# Sheet1.net
KiCad netlist of a schematic drawn in Altium Designer
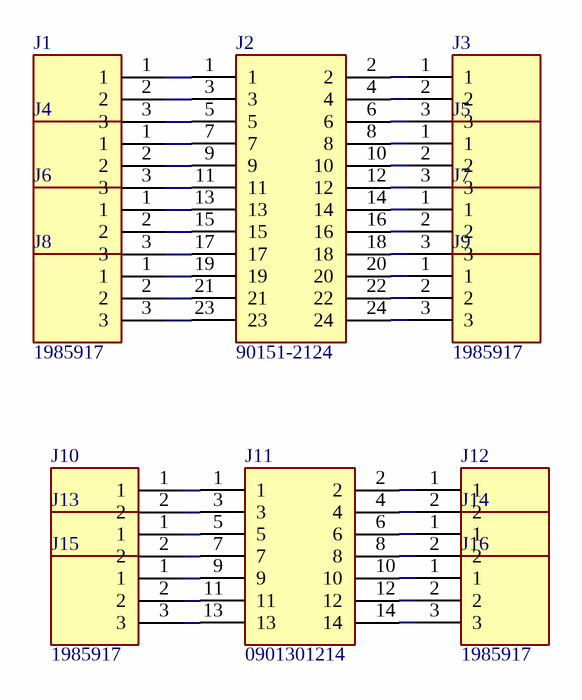
[diagram p0: Sheet1.SchDoc]

(export (version "E")
  (design (tool "Eeschema 10.0.6"))
  (components
    (comp (ref "J1")
      (value "1985917")
      (footprint "1985917")
      (description "PCB Terminal Block 1985917")
      (libsource (lib "") (part "1985917_1"))
    )
    (comp (ref "J2")
      (value "90151-2124")
      (footprint "RHDR24W64P254_2X12_3033X498X870P")
      (description "Headers & Wire Housings C-Grid PCB Conn DR Vt Tn-A 24Ckt")
      (libsource (lib "90151-2124") (part "90151-2124"))
    )
    (comp (ref "J3")
      (value "1985917")
      (footprint "1985917")
      (description "PCB Terminal Block 1985917")
      (libsource (lib "1985917") (part "1985917"))
    )
    (comp (ref "J4")
      (value "1985917")
      (footprint "1985917")
      (description "PCB Terminal Block 1985917")
      (libsource (lib "") (part "1985917_1"))
    )
    (comp (ref "J5")
      (value "1985917")
      (footprint "1985917")
      (description "PCB Terminal Block 1985917")
      (libsource (lib "1985917") (part "1985917"))
    )
    (comp (ref "J6")
      (value "1985917")
      (footprint "1985917")
      (description "PCB Terminal Block 1985917")
      (libsource (lib "") (part "1985917_1"))
    )
    (comp (ref "J7")
      (value "1985917")
      (footprint "1985917")
      (description "PCB Terminal Block 1985917")
      (libsource (lib "1985917") (part "1985917"))
    )
    (comp (ref "J8")
      (value "1985917")
      (footprint "1985917")
      (description "PCB Terminal Block 1985917")
      (libsource (lib "") (part "1985917_1"))
    )
    (comp (ref "J9")
      (value "1985917")
      (footprint "1985917")
      (description "PCB Terminal Block 1985917")
      (libsource (lib "1985917") (part "1985917"))
    )
    (comp (ref "J10") (value "1711725") (footprint "1711725") (libsource (lib "") (part "1711725_1")))
    (comp (ref "J11")
      (value "0901301214")
      (footprint "SHDR14W65P254_2X7_2012X975X1110P")
      (description "Headers & Wire Housings C-GRID III 2.54MM VT SHRD 2X07")
      (libsource (lib "0901301214") (part "0901301214"))
    )
    (comp (ref "J12") (value "1711725") (footprint "1711725") (libsource (lib "1711725") (part "1711725")))
    (comp (ref "J13") (value "1711725") (footprint "1711725") (libsource (lib "") (part "1711725_1")))
    (comp (ref "J14") (value "1711725") (footprint "1711725") (libsource (lib "1711725") (part "1711725")))
    (comp (ref "J15")
      (value "1985917")
      (footprint "1985917")
      (description "PCB Terminal Block 1985917")
      (libsource (lib "") (part "1985917_1"))
    )
    (comp (ref "J16")
      (value "1985917")
      (footprint "1985917")
      (description "PCB Terminal Block 1985917")
      (libsource (lib "1985917") (part "1985917"))
    )
  )
  (nets
    (net (code "1") (name "Net-(J1-Pad1)") (class "Default")
      (node (ref "J1") (pin "1") (pinfunction "1_1") (pintype "passive"))
      (node (ref "J2") (pin "1") (pinfunction "1_1") (pintype "passive"))
    )
    (net (code "2") (name "Net-(J1-Pad2)") (class "Default")
      (node (ref "J1") (pin "2") (pinfunction "2_2") (pintype "passive"))
      (node (ref "J2") (pin "3") (pinfunction "3_3") (pintype "passive"))
    )
    (net (code "3") (name "Net-(J1-Pad3)") (class "Default")
      (node (ref "J1") (pin "3") (pinfunction "3_3") (pintype "passive"))
      (node (ref "J2") (pin "5") (pinfunction "5_5") (pintype "passive"))
    )
    (net (code "4") (name "Net-(J2-Pad2)") (class "Default")
      (node (ref "J2") (pin "2") (pinfunction "2_2") (pintype "passive"))
      (node (ref "J3") (pin "1") (pinfunction "1_1") (pintype "passive"))
    )
    (net (code "5") (name "Net-(J2-Pad4)") (class "Default")
      (node (ref "J2") (pin "4") (pinfunction "4_4") (pintype "passive"))
      (node (ref "J3") (pin "2") (pinfunction "2_2") (pintype "passive"))
    )
    (net (code "6") (name "Net-(J2-Pad6)") (class "Default")
      (node (ref "J2") (pin "6") (pinfunction "6_6") (pintype "passive"))
      (node (ref "J3") (pin "3") (pinfunction "3_3") (pintype "passive"))
    )
    (net (code "7") (name "Net-(J2-Pad7)") (class "Default")
      (node (ref "J2") (pin "7") (pinfunction "7_7") (pintype "passive"))
      (node (ref "J4") (pin "1") (pinfunction "1_1") (pintype "passive"))
    )
    (net (code "8") (name "Net-(J2-Pad8)") (class "Default")
      (node (ref "J2") (pin "8") (pinfunction "8_8") (pintype "passive"))
      (node (ref "J5") (pin "1") (pinfunction "1_1") (pintype "passive"))
    )
    (net (code "9") (name "Net-(J2-Pad9)") (class "Default")
      (node (ref "J2") (pin "9") (pinfunction "9_9") (pintype "passive"))
      (node (ref "J4") (pin "2") (pinfunction "2_2") (pintype "passive"))
    )
    (net (code "10") (name "Net-(J2-Pad10)") (class "Default")
      (node (ref "J2") (pin "10") (pinfunction "10_10") (pintype "passive"))
      (node (ref "J5") (pin "2") (pinfunction "2_2") (pintype "passive"))
    )
    (net (code "11") (name "Net-(J2-Pad11)") (class "Default")
      (node (ref "J2") (pin "11") (pinfunction "11_11") (pintype "passive"))
      (node (ref "J4") (pin "3") (pinfunction "3_3") (pintype "passive"))
    )
    (net (code "12") (name "Net-(J2-Pad12)") (class "Default")
      (node (ref "J2") (pin "12") (pinfunction "12_12") (pintype "passive"))
      (node (ref "J5") (pin "3") (pinfunction "3_3") (pintype "passive"))
    )
    (net (code "13") (name "Net-(J2-Pad13)") (class "Default")
      (node (ref "J2") (pin "13") (pinfunction "13_13") (pintype "passive"))
      (node (ref "J6") (pin "1") (pinfunction "1_1") (pintype "passive"))
    )
    (net (code "14") (name "Net-(J2-Pad14)") (class "Default")
      (node (ref "J2") (pin "14") (pinfunction "14_14") (pintype "passive"))
      (node (ref "J7") (pin "1") (pinfunction "1_1") (pintype "passive"))
    )
    (net (code "15") (name "Net-(J2-Pad15)") (class "Default")
      (node (ref "J2") (pin "15") (pinfunction "15_15") (pintype "passive"))
      (node (ref "J6") (pin "2") (pinfunction "2_2") (pintype "passive"))
    )
    (net (code "16") (name "Net-(J2-Pad16)") (class "Default")
      (node (ref "J2") (pin "16") (pinfunction "16_16") (pintype "passive"))
      (node (ref "J7") (pin "2") (pinfunction "2_2") (pintype "passive"))
    )
    (net (code "17") (name "Net-(J2-Pad17)") (class "Default")
      (node (ref "J2") (pin "17") (pinfunction "17_17") (pintype "passive"))
      (node (ref "J6") (pin "3") (pinfunction "3_3") (pintype "passive"))
    )
    (net (code "18") (name "Net-(J2-Pad18)") (class "Default")
      (node (ref "J2") (pin "18") (pinfunction "18_18") (pintype "passive"))
      (node (ref "J7") (pin "3") (pinfunction "3_3") (pintype "passive"))
    )
    (net (code "19") (name "Net-(J2-Pad19)") (class "Default")
      (node (ref "J2") (pin "19") (pinfunction "19_19") (pintype "passive"))
      (node (ref "J8") (pin "1") (pinfunction "1_1") (pintype "passive"))
    )
    (net (code "20") (name "Net-(J2-Pad20)") (class "Default")
      (node (ref "J2") (pin "20") (pinfunction "20_20") (pintype "passive"))
      (node (ref "J9") (pin "1") (pinfunction "1_1") (pintype "passive"))
    )
    (net (code "21") (name "Net-(J2-Pad21)") (class "Default")
      (node (ref "J2") (pin "21") (pinfunction "21_21") (pintype "passive"))
      (node (ref "J8") (pin "2") (pinfunction "2_2") (pintype "passive"))
    )
    (net (code "22") (name "Net-(J2-Pad22)") (class "Default")
      (node (ref "J2") (pin "22") (pinfunction "22_22") (pintype "passive"))
      (node (ref "J9") (pin "2") (pinfunction "2_2") (pintype "passive"))
    )
    (net (code "23") (name "Net-(J2-Pad23)") (class "Default")
      (node (ref "J2") (pin "23") (pinfunction "23_23") (pintype "passive"))
      (node (ref "J8") (pin "3") (pinfunction "3_3") (pintype "passive"))
    )
    (net (code "24") (name "Net-(J2-Pad24)") (class "Default")
      (node (ref "J2") (pin "24") (pinfunction "24_24") (pintype "passive"))
      (node (ref "J9") (pin "3") (pinfunction "3_3") (pintype "passive"))
    )
    (net (code "25") (name "Net-(J10-Pad1)") (class "Default")
      (node (ref "J10") (pin "1") (pinfunction "1_1") (pintype "passive"))
      (node (ref "J11") (pin "1") (pinfunction "1_1") (pintype "passive"))
    )
    (net (code "26") (name "Net-(J10-Pad2)") (class "Default")
      (node (ref "J10") (pin "2") (pinfunction "2_2") (pintype "passive"))
      (node (ref "J11") (pin "3") (pinfunction "3_3") (pintype "passive"))
    )
    (net (code "27") (name "Net-(J11-Pad2)") (class "Default")
      (node (ref "J11") (pin "2") (pinfunction "2_2") (pintype "passive"))
      (node (ref "J12") (pin "1") (pinfunction "1_1") (pintype "passive"))
    )
    (net (code "28") (name "Net-(J11-Pad4)") (class "Default")
      (node (ref "J11") (pin "4") (pinfunction "4_4") (pintype "passive"))
      (node (ref "J12") (pin "2") (pinfunction "2_2") (pintype "passive"))
    )
    (net (code "29") (name "Net-(J11-Pad5)") (class "Default")
      (node (ref "J11") (pin "5") (pinfunction "5_5") (pintype "passive"))
      (node (ref "J13") (pin "1") (pinfunction "1_1") (pintype "passive"))
    )
    (net (code "30") (name "Net-(J11-Pad6)") (class "Default")
      (node (ref "J11") (pin "6") (pinfunction "6_6") (pintype "passive"))
      (node (ref "J14") (pin "1") (pinfunction "1_1") (pintype "passive"))
    )
    (net (code "31") (name "Net-(J11-Pad7)") (class "Default")
      (node (ref "J11") (pin "7") (pinfunction "7_7") (pintype "passive"))
      (node (ref "J13") (pin "2") (pinfunction "2_2") (pintype "passive"))
    )
    (net (code "32") (name "Net-(J11-Pad8)") (class "Default")
      (node (ref "J11") (pin "8") (pinfunction "8_8") (pintype "passive"))
      (node (ref "J14") (pin "2") (pinfunction "2_2") (pintype "passive"))
    )
    (net (code "33") (name "Net-(J11-Pad9)") (class "Default")
      (node (ref "J11") (pin "9") (pinfunction "9_9") (pintype "passive"))
      (node (ref "J15") (pin "1") (pinfunction "1_1") (pintype "passive"))
    )
    (net (code "34") (name "Net-(J11-Pad10)") (class "Default")
      (node (ref "J11") (pin "10") (pinfunction "10_10") (pintype "passive"))
      (node (ref "J16") (pin "1") (pinfunction "1_1") (pintype "passive"))
    )
    (net (code "35") (name "Net-(J11-Pad11)") (class "Default")
      (node (ref "J11") (pin "11") (pinfunction "11_11") (pintype "passive"))
      (node (ref "J15") (pin "2") (pinfunction "2_2") (pintype "passive"))
    )
    (net (code "36") (name "Net-(J11-Pad12)") (class "Default")
      (node (ref "J11") (pin "12") (pinfunction "12_12") (pintype "passive"))
      (node (ref "J16") (pin "2") (pinfunction "2_2") (pintype "passive"))
    )
    (net (code "37") (name "Net-(J11-Pad13)") (class "Default")
      (node (ref "J11") (pin "13") (pinfunction "13_13") (pintype "passive"))
      (node (ref "J15") (pin "3") (pinfunction "3_3") (pintype "passive"))
    )
    (net (code "38") (name "Net-(J11-Pad14)") (class "Default")
      (node (ref "J11") (pin "14") (pinfunction "14_14") (pintype "passive"))
      (node (ref "J16") (pin "3") (pinfunction "3_3") (pintype "passive"))
    )
  )
)
